# OIS_Relay.net
KiCad netlist of a schematic drawn in Altium Designer
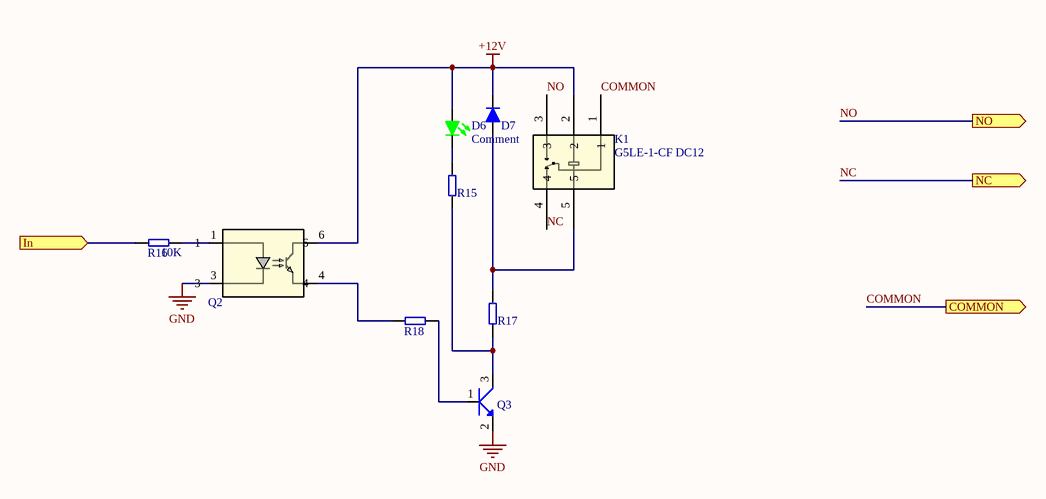
[diagram p0: OIS_Relay.SchDoc]

(export (version "E")
  (design (tool "Eeschema 10.0.6"))
  (components
    (comp (ref "D6")
      (value "Comment")
      (footprint "L0402_A")
      (description "LED RED CLEAR 0402 SMD")
      (fields (field (name "PART NUMBER") "SML-P12VTT86R"))
      (libsource (lib "anayurt") (part "LED_RED"))
    )
    (comp (ref "D7")
      (value "TSSA3U60 R3G")
      (footprint "TAIWAN_TSSA3U60 R3G")
      (description "DIODE SCHOTTKY 60V 3A DO214AC")
      (fields (field (name "MANUFACTURER") "Taiwan Semiconductor Corporation"))
      (libsource (lib "anayurt") (part "DIODE"))
    )
    (comp (ref "K1")
      (value "G5LE-1-CF DC12")
      (footprint "RELAY_G5LE-1 DC5_OMR")
      (fields (field (name "COPYRIGHT") "Copyright (C) 2023 Ultra Librarian. All rights reserved."))
      (libsource (lib "anayurt") (part "G5LE-1-CF DC12"))
    )
    (comp (ref "Q2")
      (value "TLP188(TPL,E")
      (footprint "OptoCoupler")
      (description "IC-188 OPTOISO 3.75KV TRANS SO6")
      (fields (field (name "COPYRIGHT") "Copyright (C) 2023 Ultra Librarian. All rights reserved."))
      (libsource (lib "anayurt") (part "OptoCoupler"))
    )
    (comp (ref "Q3")
      (value "MMBT4401-7-F")
      (footprint "SOT-23")
      (description "TRANS NPN 40V 0.6A SMD SOT23-3")
      (fields (field (name "MANUFACTURER") "Diodes Incorporated"))
      (libsource (lib "anayurt") (part "NPN"))
    )
    (comp (ref "R15")
      (value "1K")
      (footprint "R0402")
      (description "RES SMD 1K OHM 0.1% 1/16W 0402")
      (fields (field (name "PART NUMBER") "RT0402BRE071KL") (field (name "TOLERANCE") "0.1%"))
      (libsource (lib "anayurt") (part "RES"))
    )
    (comp (ref "R16")
      (value "10K")
      (footprint "R0402")
      (description "RES SMD 10K OHM 1% 1/16W 0402")
      (fields (field (name "PART NUMBER") "RC1005F103CS") (field (name "TOLERANCE") "0.1%"))
      (libsource (lib "anayurt") (part "RES"))
    )
    (comp (ref "R17")
      (value "1K")
      (footprint "R0402")
      (description "RES SMD 1K OHM 0.1% 1/16W 0402")
      (fields (field (name "PART NUMBER") "RT0402BRE071KL") (field (name "TOLERANCE") "0.1%"))
      (libsource (lib "anayurt") (part "RES"))
    )
    (comp (ref "R18")
      (value "1K")
      (footprint "R0402")
      (description "RES SMD 1K OHM 0.1% 1/16W 0402")
      (fields (field (name "PART NUMBER") "RT0402BRE071KL") (field (name "TOLERANCE") "0.1%"))
      (libsource (lib "anayurt") (part "RES"))
    )
  )
  (nets
    (net (code "1") (name "+12V") (class "Default")
      (node (ref "D6") (pin "A") (pinfunction "A_A") (pintype "passive"))
      (node (ref "D7") (pin "C") (pinfunction "C_C") (pintype "passive"))
      (node (ref "K1") (pin "2") (pinfunction "2_2") (pintype "passive"))
      (node (ref "Q2") (pin "6") (pinfunction "6_6") (pintype "passive"))
    )
    (net (code "2") (name "/COMMON") (class "Default")
      (node (ref "K1") (pin "1") (pinfunction "1_1") (pintype "passive"))
    )
    (net (code "3") (name "/In") (class "Default")
      (node (ref "R16") (pin "1") (pinfunction "1_1") (pintype "passive"))
    )
    (net (code "4") (name "/NC") (class "Default")
      (node (ref "K1") (pin "4") (pinfunction "4_4") (pintype "passive"))
    )
    (net (code "5") (name "/NO") (class "Default")
      (node (ref "K1") (pin "3") (pinfunction "3_3") (pintype "passive"))
    )
    (net (code "6") (name "GND") (class "Default")
      (node (ref "Q2") (pin "3") (pinfunction "3_3") (pintype "passive"))
      (node (ref "Q3") (pin "2") (pinfunction "E_2") (pintype "passive"))
    )
    (net (code "7") (name "Net-(D6-PadC)") (class "Default")
      (node (ref "D6") (pin "C") (pinfunction "C_C") (pintype "passive"))
      (node (ref "R15") (pin "2") (pinfunction "2_2") (pintype "passive"))
    )
    (net (code "8") (name "Net-(D7-PadA)") (class "Default")
      (node (ref "D7") (pin "A") (pinfunction "A_A") (pintype "passive"))
      (node (ref "K1") (pin "5") (pinfunction "5_5") (pintype "passive"))
      (node (ref "R17") (pin "2") (pinfunction "2_2") (pintype "passive"))
    )
    (net (code "9") (name "Net-(Q2-Pad1)") (class "Default")
      (node (ref "Q2") (pin "1") (pinfunction "1_1") (pintype "passive"))
      (node (ref "R16") (pin "2") (pinfunction "2_2") (pintype "passive"))
    )
    (net (code "10") (name "Net-(Q2-Pad4)") (class "Default")
      (node (ref "Q2") (pin "4") (pinfunction "4_4") (pintype "passive"))
      (node (ref "R18") (pin "1") (pinfunction "1_1") (pintype "passive"))
    )
    (net (code "11") (name "Net-(Q3-B)") (class "Default")
      (node (ref "Q3") (pin "1") (pinfunction "B_1") (pintype "passive"))
      (node (ref "R18") (pin "2") (pinfunction "2_2") (pintype "passive"))
    )
    (net (code "12") (name "Net-(Q3-C)") (class "Default")
      (node (ref "Q3") (pin "3") (pinfunction "C_3") (pintype "passive"))
      (node (ref "R15") (pin "1") (pinfunction "1_1") (pintype "passive"))
      (node (ref "R17") (pin "1") (pinfunction "1_1") (pintype "passive"))
    )
  )
)
